# GyroAccel.net
KiCad netlist of a schematic drawn in Altium Designer
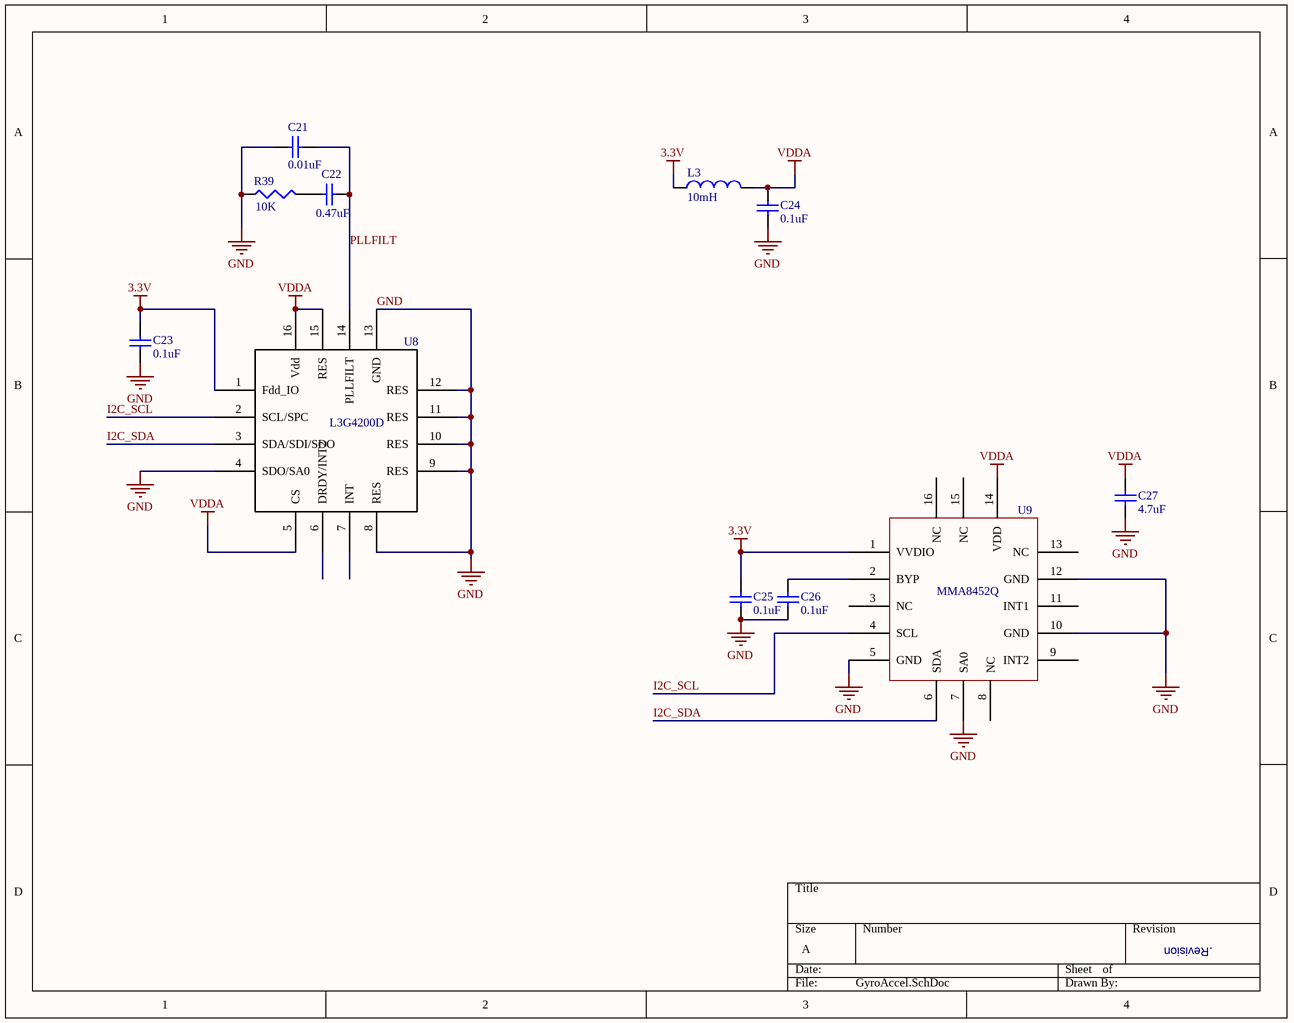
[diagram p0: GyroAccel.SchDoc]

(export (version "E")
  (design (tool "Eeschema 10.0.6"))
  (components
    (comp (ref "C21")
      (value "0.01uF")
      (footprint "CAPC1005L")
      (description "Capacitor (Semiconductor SIM Model)")
      (fields
        (field (name "PART NUMBER") "UMK105B7103KV-F")
        (field (name "MANUFACTURER") "Taiyo Yuden")
        (field (name "PUBLISHER") "Altium Limited")
      )
      (libsource (lib "Miscellaneous Devices") (part "Cap Semi"))
    )
    (comp (ref "C22")
      (value "0.47uF")
      (footprint "CAPC1005L")
      (description "Capacitor (Semiconductor SIM Model)")
      (fields
        (field (name "PART NUMBER") "GRM155F51C474ZA01D")
        (field (name "MANUFACTURER") "Murata")
        (field (name "PUBLISHER") "Altium Limited")
      )
      (libsource (lib "Miscellaneous Devices") (part "Cap Semi"))
    )
    (comp (ref "C23")
      (value "0.1uF")
      (footprint "CAPC1005L")
      (description "Capacitor (Semiconductor SIM Model)")
      (fields
        (field (name "PART NUMBER") "GRM155R71C104KA88D")
        (field (name "MANUFACTURER") "Murata")
        (field (name "PUBLISHER") "Altium Limited")
      )
      (libsource (lib "Miscellaneous Devices") (part "Cap Semi"))
    )
    (comp (ref "C24")
      (value "0.1uF")
      (footprint "CAPC1005L")
      (description "Capacitor (Semiconductor SIM Model)")
      (fields
        (field (name "PART NUMBER") "GRM155R71C104KA88D")
        (field (name "MANUFACTURER") "Murata")
        (field (name "PUBLISHER") "Altium Limited")
      )
      (libsource (lib "Miscellaneous Devices") (part "Cap Semi"))
    )
    (comp (ref "C25")
      (value "0.1uF")
      (footprint "CAPC1005L")
      (description "Capacitor (Semiconductor SIM Model)")
      (fields
        (field (name "PART NUMBER") "GRM155R71C104KA88D")
        (field (name "MANUFACTURER") "Murata")
        (field (name "PUBLISHER") "Altium Limited")
      )
      (libsource (lib "Miscellaneous Devices") (part "Cap Semi"))
    )
    (comp (ref "C26")
      (value "0.1uF")
      (footprint "CAPC1005L")
      (description "Capacitor (Semiconductor SIM Model)")
      (fields
        (field (name "PART NUMBER") "GRM155R71C104KA88D")
        (field (name "MANUFACTURER") "Murata")
        (field (name "PUBLISHER") "Altium Limited")
      )
      (libsource (lib "Miscellaneous Devices") (part "Cap Semi"))
    )
    (comp (ref "C27")
      (value "4.7uF")
      (footprint "CAPC1608L")
      (description "Capacitor (Semiconductor SIM Model)")
      (fields
        (field (name "PART NUMBER") "JMK107BJ475KA-T")
        (field (name "MANUFACTURER") "Taiyo Yuden")
        (field (name "PUBLISHER") "Altium Limited")
      )
      (libsource (lib "Miscellaneous Devices") (part "Cap Semi"))
    )
    (comp (ref "L3")
      (value "10mH")
      (footprint "INDC2012L")
      (description "Inductor")
      (fields
        (field (name "PART NUMBER") "MMZ2012R102A")
        (field (name "MANUFACTURER") "TDK")
        (field (name "PUBLISHER") "Altium Limited")
      )
      (libsource (lib "Miscellaneous Devices") (part "Inductor"))
    )
    (comp (ref "R39")
      (value "10K")
      (footprint "RESC1608L")
      (description "Resistor")
      (fields
        (field (name "PART NUMBER") "71-CRCW0603-10K-E3")
        (field (name "MANUFACTURER") "Vishay Dale")
        (field (name "PUBLISHER") "Altium Limited")
      )
      (libsource (lib "Miscellaneous Devices") (part "Res3"))
    )
    (comp (ref "U8")
      (value "L3G4200D")
      (footprint "L3G2004D")
      (description "3axis gyroscope, SPI")
      (fields (field (name "PART NUMBER") "L3G4200DTR") (field (name "MANUFACTURER") "ST Mircoelectronics"))
      (libsource (lib "mrone") (part "L3G4200D"))
    )
    (comp (ref "U9")
      (value "MMA8452Q")
      (footprint "MMA8452Q")
      (fields
        (field (name "PART NUMBER") "MMA8452QT")
        (field (name "MANUFACTURER") "Freescale Semiconductor")
      )
      (libsource (lib "mrone") (part "MMA8452Q"))
    )
  )
  (nets
    (net (code "1") (name "/I2C_SCL") (class "Default")
      (node (ref "U8") (pin "2") (pinfunction "SCL/SPC_2") (pintype "passive"))
      (node (ref "U9") (pin "4") (pinfunction "SCL_4") (pintype "passive"))
    )
    (net (code "2") (name "/I2C_SDA") (class "Default")
      (node (ref "U8") (pin "3") (pinfunction "SDA/SDI/SDO_3") (pintype "passive"))
      (node (ref "U9") (pin "6") (pinfunction "SDA_6") (pintype "passive"))
    )
    (net (code "3") (name "/PLLFILT") (class "Default")
      (node (ref "C21") (pin "1") (pinfunction "1_1") (pintype "passive"))
      (node (ref "C22") (pin "1") (pinfunction "1_1") (pintype "passive"))
      (node (ref "U8") (pin "14") (pinfunction "PLLFILT_14") (pintype "passive"))
    )
    (net (code "4") (name "3.3V") (class "Default")
      (node (ref "C23") (pin "2") (pinfunction "2_2") (pintype "passive"))
      (node (ref "C25") (pin "2") (pinfunction "2_2") (pintype "passive"))
      (node (ref "L3") (pin "2") (pinfunction "2_2") (pintype "passive"))
      (node (ref "U8") (pin "1") (pinfunction "Fdd_IO_1") (pintype "passive"))
      (node (ref "U9") (pin "1") (pinfunction "VVDIO_1") (pintype "passive"))
    )
    (net (code "5") (name "GND") (class "Default")
      (node (ref "C21") (pin "2") (pinfunction "2_2") (pintype "passive"))
      (node (ref "C23") (pin "1") (pinfunction "1_1") (pintype "passive"))
      (node (ref "C24") (pin "1") (pinfunction "1_1") (pintype "passive"))
      (node (ref "C25") (pin "1") (pinfunction "1_1") (pintype "passive"))
      (node (ref "C26") (pin "1") (pinfunction "1_1") (pintype "passive"))
      (node (ref "C27") (pin "1") (pinfunction "1_1") (pintype "passive"))
      (node (ref "R39") (pin "1") (pinfunction "1_1") (pintype "passive"))
      (node (ref "U8") (pin "10") (pinfunction "RES_10") (pintype "passive"))
      (node (ref "U8") (pin "11") (pinfunction "RES_11") (pintype "passive"))
      (node (ref "U8") (pin "12") (pinfunction "RES_12") (pintype "passive"))
      (node (ref "U8") (pin "13") (pinfunction "GND_13") (pintype "passive"))
      (node (ref "U8") (pin "4") (pinfunction "SDO/SA0_4") (pintype "passive"))
      (node (ref "U8") (pin "8") (pinfunction "RES_8") (pintype "passive"))
      (node (ref "U8") (pin "9") (pinfunction "RES_9") (pintype "passive"))
      (node (ref "U9") (pin "10") (pinfunction "GND_10") (pintype "passive"))
      (node (ref "U9") (pin "12") (pinfunction "GND_12") (pintype "passive"))
      (node (ref "U9") (pin "5") (pinfunction "GND_5") (pintype "passive"))
      (node (ref "U9") (pin "7") (pinfunction "SA0_7") (pintype "passive"))
    )
    (net (code "6") (name "Net-(C22-Pad2)") (class "Default")
      (node (ref "C22") (pin "2") (pinfunction "2_2") (pintype "passive"))
      (node (ref "R39") (pin "2") (pinfunction "2_2") (pintype "passive"))
    )
    (net (code "7") (name "Net-(U9-BYP)") (class "Default")
      (node (ref "C26") (pin "2") (pinfunction "2_2") (pintype "passive"))
      (node (ref "U9") (pin "2") (pinfunction "BYP_2") (pintype "passive"))
    )
    (net (code "8") (name "VDDA") (class "Default")
      (node (ref "C24") (pin "2") (pinfunction "2_2") (pintype "passive"))
      (node (ref "C27") (pin "2") (pinfunction "2_2") (pintype "passive"))
      (node (ref "L3") (pin "1") (pinfunction "1_1") (pintype "passive"))
      (node (ref "U8") (pin "15") (pinfunction "RES_15") (pintype "passive"))
      (node (ref "U8") (pin "16") (pinfunction "Vdd_16") (pintype "passive"))
      (node (ref "U8") (pin "5") (pinfunction "CS_5") (pintype "passive"))
      (node (ref "U9") (pin "14") (pinfunction "VDD_14") (pintype "passive"))
    )
    (net (code "9") (name "unconnected-(U8-DRDY{slash}INT2-Pad6)") (class "Default")
      (node (ref "U8") (pin "6") (pinfunction "DRDY/INT2_6") (pintype "passive"))
    )
    (net (code "10") (name "unconnected-(U8-INT-Pad7)") (class "Default")
      (node (ref "U8") (pin "7") (pinfunction "INT_7") (pintype "passive"))
    )
    (net (code "11") (name "unconnected-(U9-INT1-Pad11)") (class "Default")
      (node (ref "U9") (pin "11") (pinfunction "INT1_11") (pintype "passive"))
    )
    (net (code "12") (name "unconnected-(U9-INT2-Pad9)") (class "Default")
      (node (ref "U9") (pin "9") (pinfunction "INT2_9") (pintype "passive"))
    )
    (net (code "13") (name "unconnected-(U9-NC-Pad3)") (class "Default")
      (node (ref "U9") (pin "3") (pinfunction "NC_3") (pintype "passive"))
    )
    (net (code "14") (name "unconnected-(U9-NC-Pad8)") (class "Default")
      (node (ref "U9") (pin "8") (pinfunction "NC_8") (pintype "passive"))
    )
    (net (code "15") (name "unconnected-(U9-NC-Pad13)") (class "Default")
      (node (ref "U9") (pin "13") (pinfunction "NC_13") (pintype "passive"))
    )
    (net (code "16") (name "unconnected-(U9-NC-Pad15)") (class "Default")
      (node (ref "U9") (pin "15") (pinfunction "NC_15") (pintype "passive"))
    )
    (net (code "17") (name "unconnected-(U9-NC-Pad16)") (class "Default")
      (node (ref "U9") (pin "16") (pinfunction "NC_16") (pintype "passive"))
    )
  )
)
